# ENGI301_PCB_design_project.net
KiCad netlist of a schematic drawn in EAGLE
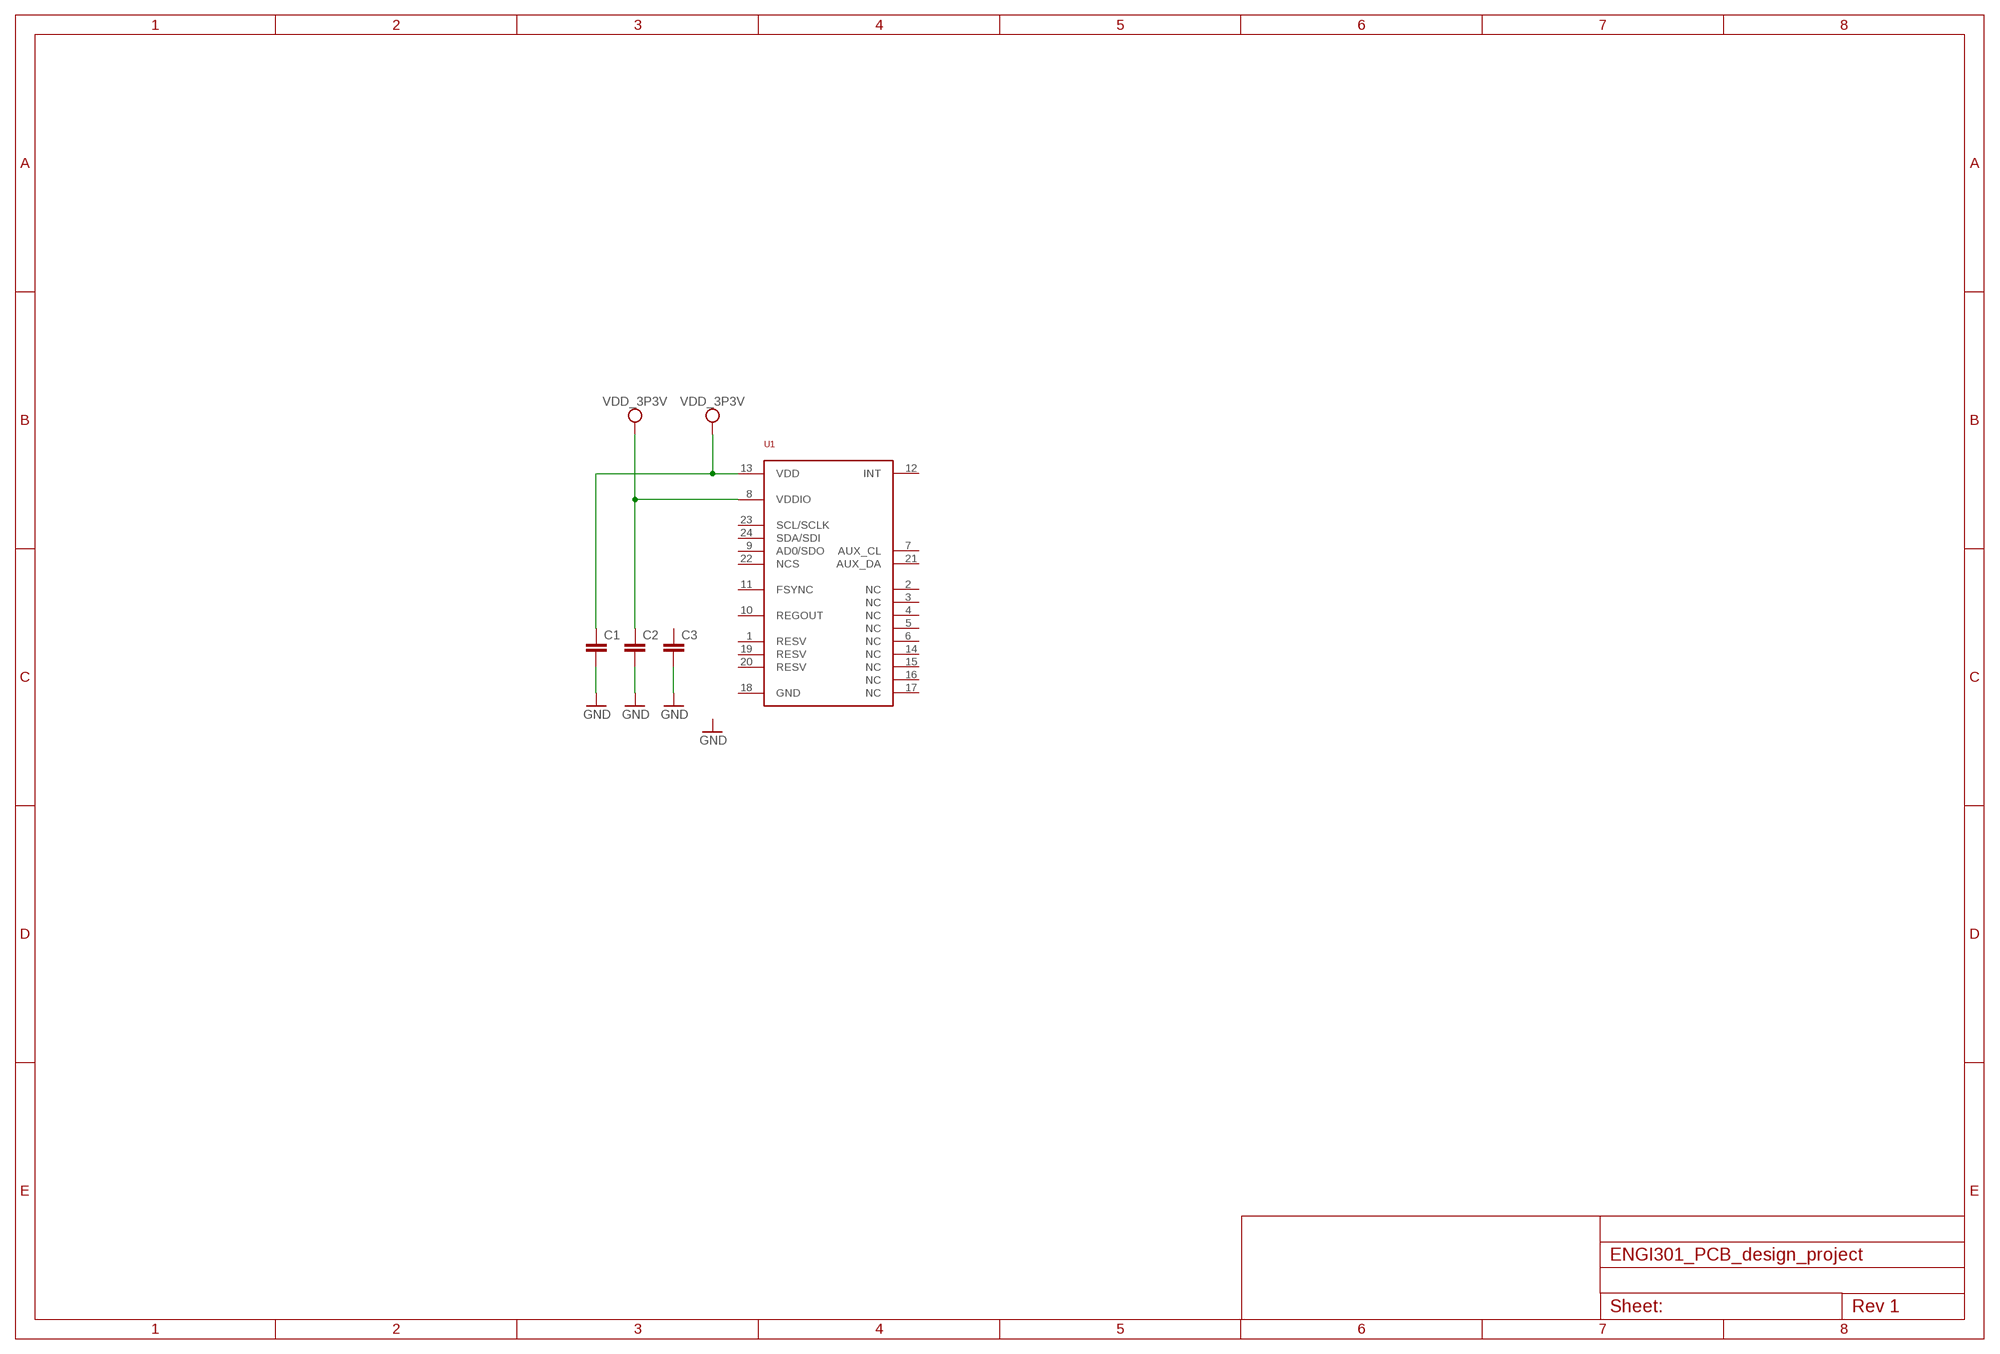
[diagram p0: schematic, sheet 1]

(export (version "E")
  (design (tool "Eeschema 10.0.6"))
  (components
    (comp (ref "C1")
      (value "C_C0402")
      (footprint "eagle-import:C0402")
      (libsource (lib "eagle-import") (part "C_C0402"))
    )
    (comp (ref "C2")
      (value "C_C0402")
      (footprint "eagle-import:C0402")
      (libsource (lib "eagle-import") (part "C_C0402"))
    )
    (comp (ref "C3")
      (value "C_C0402")
      (footprint "eagle-import:C0402")
      (libsource (lib "eagle-import") (part "C_C0402"))
    )
    (comp (ref "U1")
      (value "MPU-9250")
      (footprint "eagle-import:QFN-3MMX3MM")
      (libsource (lib "eagle-import") (part "MPU-9250"))
    )
  )
  (nets
    (net (code "1") (name "GND") (class "Default")
      (node (ref "C1") (pin "2") (pinfunction "2_2") (pintype "passive"))
      (node (ref "C2") (pin "2") (pinfunction "2_2") (pintype "passive"))
      (node (ref "C3") (pin "2") (pinfunction "2_2") (pintype "passive"))
    )
    (net (code "2") (name "VDD_3P3V") (class "Default")
      (node (ref "C1") (pin "1") (pinfunction "1_1") (pintype "passive"))
      (node (ref "C2") (pin "1") (pinfunction "1_1") (pintype "passive"))
      (node (ref "U1") (pin "13") (pinfunction "VDD_13") (pintype "bidirectional"))
      (node (ref "U1") (pin "8") (pinfunction "VDDIO_8") (pintype "bidirectional"))
    )
    (net (code "3") (name "unconnected-(C3-Pad1)") (class "Default")
      (node (ref "C3") (pin "1") (pinfunction "1_1") (pintype "passive"))
    )
    (net (code "4") (name "unconnected-(U1-AD0{slash}SDO-Pad9)") (class "Default")
      (node (ref "U1") (pin "9") (pinfunction "AD0/SDO_9") (pintype "bidirectional"))
    )
    (net (code "5") (name "unconnected-(U1-AUX_CL-Pad7)") (class "Default")
      (node (ref "U1") (pin "7") (pinfunction "AUX_CL_7") (pintype "bidirectional"))
    )
    (net (code "6") (name "unconnected-(U1-AUX_DA-Pad21)") (class "Default")
      (node (ref "U1") (pin "21") (pinfunction "AUX_DA_21") (pintype "bidirectional"))
    )
    (net (code "7") (name "unconnected-(U1-FSYNC-Pad11)") (class "Default")
      (node (ref "U1") (pin "11") (pinfunction "FSYNC_11") (pintype "bidirectional"))
    )
    (net (code "8") (name "unconnected-(U1-GND-Pad18)") (class "Default")
      (node (ref "U1") (pin "18") (pinfunction "GND_18") (pintype "bidirectional"))
    )
    (net (code "9") (name "unconnected-(U1-INT-Pad12)") (class "Default")
      (node (ref "U1") (pin "12") (pinfunction "INT_12") (pintype "bidirectional"))
    )
    (net (code "10") (name "unconnected-(U1-NC-Pad2)") (class "Default")
      (node (ref "U1") (pin "2") (pinfunction "NC_2") (pintype "bidirectional"))
    )
    (net (code "11") (name "unconnected-(U1-NC-Pad3)") (class "Default")
      (node (ref "U1") (pin "3") (pinfunction "NC_3") (pintype "bidirectional"))
    )
    (net (code "12") (name "unconnected-(U1-NC-Pad4)") (class "Default")
      (node (ref "U1") (pin "4") (pinfunction "NC_4") (pintype "bidirectional"))
    )
    (net (code "13") (name "unconnected-(U1-NC-Pad5)") (class "Default")
      (node (ref "U1") (pin "5") (pinfunction "NC_5") (pintype "bidirectional"))
    )
    (net (code "14") (name "unconnected-(U1-NC-Pad6)") (class "Default")
      (node (ref "U1") (pin "6") (pinfunction "NC_6") (pintype "bidirectional"))
    )
    (net (code "15") (name "unconnected-(U1-NC-Pad14)") (class "Default")
      (node (ref "U1") (pin "14") (pinfunction "NC_14") (pintype "bidirectional"))
    )
    (net (code "16") (name "unconnected-(U1-NC-Pad15)") (class "Default")
      (node (ref "U1") (pin "15") (pinfunction "NC_15") (pintype "bidirectional"))
    )
    (net (code "17") (name "unconnected-(U1-NC-Pad16)") (class "Default")
      (node (ref "U1") (pin "16") (pinfunction "NC_16") (pintype "bidirectional"))
    )
    (net (code "18") (name "unconnected-(U1-NC-Pad17)") (class "Default")
      (node (ref "U1") (pin "17") (pinfunction "NC_17") (pintype "bidirectional"))
    )
    (net (code "19") (name "unconnected-(U1-NCS-Pad22)") (class "Default")
      (node (ref "U1") (pin "22") (pinfunction "NCS_22") (pintype "bidirectional"))
    )
    (net (code "20") (name "unconnected-(U1-REGOUT-Pad10)") (class "Default")
      (node (ref "U1") (pin "10") (pinfunction "REGOUT_10") (pintype "bidirectional"))
    )
    (net (code "21") (name "unconnected-(U1-RESV-Pad1)") (class "Default")
      (node (ref "U1") (pin "1") (pinfunction "RESV_1") (pintype "bidirectional"))
    )
    (net (code "22") (name "unconnected-(U1-RESV-Pad19)") (class "Default")
      (node (ref "U1") (pin "19") (pinfunction "RESV_19") (pintype "bidirectional"))
    )
    (net (code "23") (name "unconnected-(U1-RESV-Pad20)") (class "Default")
      (node (ref "U1") (pin "20") (pinfunction "RESV_20") (pintype "bidirectional"))
    )
    (net (code "24") (name "unconnected-(U1-SCL{slash}SCLK-Pad23)") (class "Default")
      (node (ref "U1") (pin "23") (pinfunction "SCL/SCLK_23") (pintype "bidirectional"))
    )
    (net (code "25") (name "unconnected-(U1-SDA{slash}SDI-Pad24)") (class "Default")
      (node (ref "U1") (pin "24") (pinfunction "SDA/SDI_24") (pintype "bidirectional"))
    )
  )
)
